# LSN_Motherboard_1_2.net
KiCad netlist of a schematic drawn in EAGLE
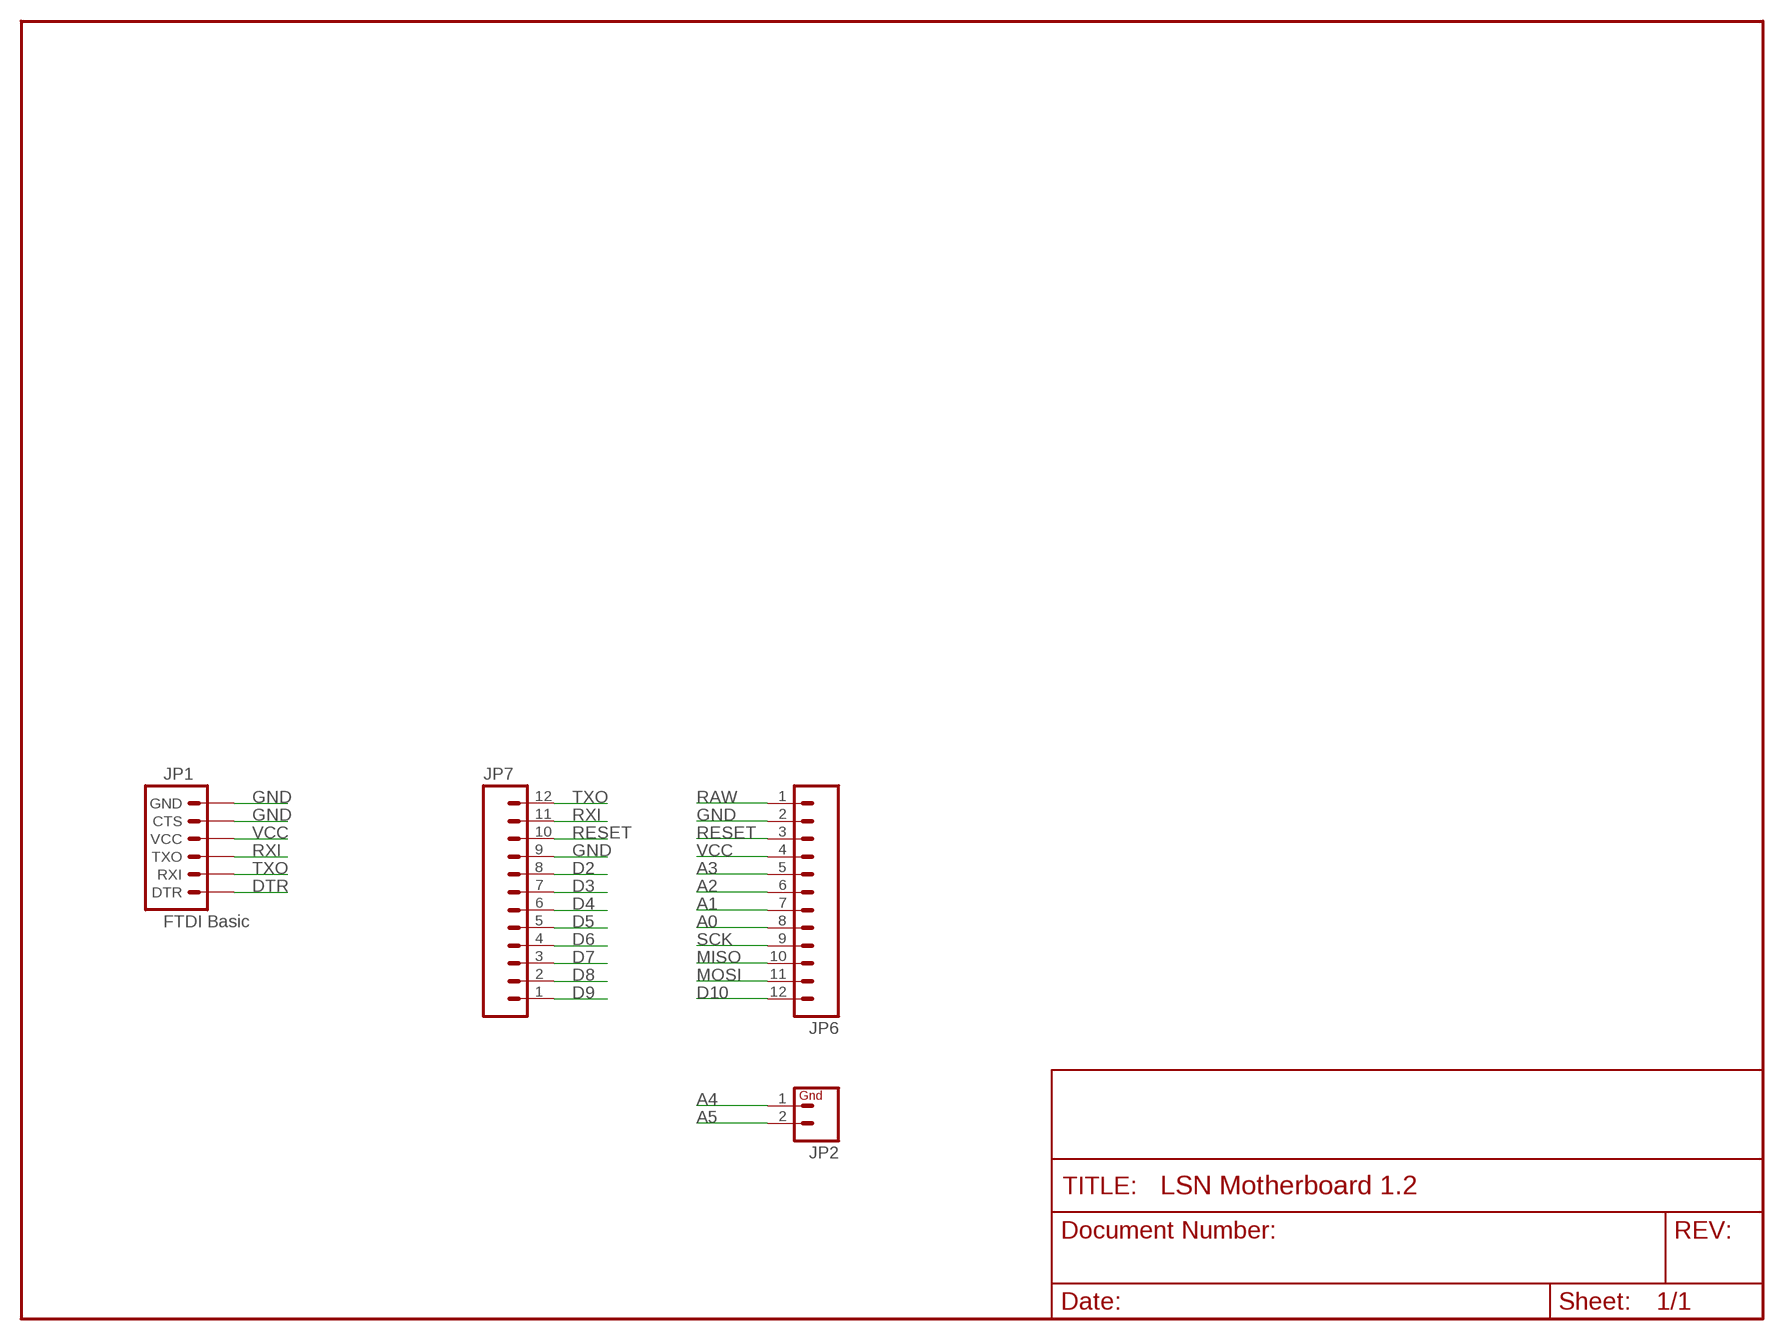
[diagram p0: schematic, sheet 1]

(export (version "E")
  (design (tool "Eeschema 10.0.6"))
  (components
    (comp (ref "JP1")
      (value "FTDI Basic")
      (footprint "eagle-import:1X06")
      (libsource (lib "eagle-import") (part "ARDUINO_SERIAL_PROGRAMPTH"))
    )
    (comp (ref "JP2")
      (value "M02PTH")
      (footprint "eagle-import:1X02")
      (libsource (lib "eagle-import") (part "M02PTH"))
    )
    (comp (ref "JP6")
      (value "M12PTH")
      (footprint "eagle-import:1X12")
      (libsource (lib "eagle-import") (part "M12PTH"))
    )
    (comp (ref "JP7")
      (value "M12PTH")
      (footprint "eagle-import:1X12")
      (libsource (lib "eagle-import") (part "M12PTH"))
    )
  )
  (nets
    (net (code "1") (name "/A0") (class "Default")
      (node (ref "JP6") (pin "8") (pinfunction "8_8") (pintype "passive"))
    )
    (net (code "2") (name "/A1") (class "Default")
      (node (ref "JP6") (pin "7") (pinfunction "7_7") (pintype "passive"))
    )
    (net (code "3") (name "/A2") (class "Default")
      (node (ref "JP6") (pin "6") (pinfunction "6_6") (pintype "passive"))
    )
    (net (code "4") (name "/A3") (class "Default")
      (node (ref "JP6") (pin "5") (pinfunction "5_5") (pintype "passive"))
    )
    (net (code "5") (name "/A4") (class "Default")
      (node (ref "JP2") (pin "1") (pinfunction "1_1") (pintype "passive"))
    )
    (net (code "6") (name "/A5") (class "Default")
      (node (ref "JP2") (pin "2") (pinfunction "2_2") (pintype "passive"))
    )
    (net (code "7") (name "/D2") (class "Default")
      (node (ref "JP7") (pin "8") (pinfunction "8_8") (pintype "passive"))
    )
    (net (code "8") (name "/D3") (class "Default")
      (node (ref "JP7") (pin "7") (pinfunction "7_7") (pintype "passive"))
    )
    (net (code "9") (name "/D4") (class "Default")
      (node (ref "JP7") (pin "6") (pinfunction "6_6") (pintype "passive"))
    )
    (net (code "10") (name "/D5") (class "Default")
      (node (ref "JP7") (pin "5") (pinfunction "5_5") (pintype "passive"))
    )
    (net (code "11") (name "/D6") (class "Default")
      (node (ref "JP7") (pin "4") (pinfunction "4_4") (pintype "passive"))
    )
    (net (code "12") (name "/D7") (class "Default")
      (node (ref "JP7") (pin "3") (pinfunction "3_3") (pintype "passive"))
    )
    (net (code "13") (name "/D8") (class "Default")
      (node (ref "JP7") (pin "2") (pinfunction "2_2") (pintype "passive"))
    )
    (net (code "14") (name "/D9") (class "Default")
      (node (ref "JP7") (pin "1") (pinfunction "1_1") (pintype "passive"))
    )
    (net (code "15") (name "/D10") (class "Default")
      (node (ref "JP6") (pin "12") (pinfunction "12_12") (pintype "passive"))
    )
    (net (code "16") (name "/DTR") (class "Default")
      (node (ref "JP1") (pin "1") (pinfunction "DTR_1") (pintype "passive"))
    )
    (net (code "17") (name "/GND") (class "Default")
      (node (ref "JP1") (pin "5") (pinfunction "CTS_5") (pintype "passive"))
      (node (ref "JP1") (pin "6") (pinfunction "GND_6") (pintype "passive"))
      (node (ref "JP6") (pin "2") (pinfunction "2_2") (pintype "passive"))
      (node (ref "JP7") (pin "9") (pinfunction "9_9") (pintype "passive"))
    )
    (net (code "18") (name "/MISO") (class "Default")
      (node (ref "JP6") (pin "10") (pinfunction "10_10") (pintype "passive"))
    )
    (net (code "19") (name "/MOSI") (class "Default")
      (node (ref "JP6") (pin "11") (pinfunction "11_11") (pintype "passive"))
    )
    (net (code "20") (name "/RAW") (class "Default")
      (node (ref "JP6") (pin "1") (pinfunction "1_1") (pintype "passive"))
    )
    (net (code "21") (name "/RESET") (class "Default")
      (node (ref "JP6") (pin "3") (pinfunction "3_3") (pintype "passive"))
      (node (ref "JP7") (pin "10") (pinfunction "10_10") (pintype "passive"))
    )
    (net (code "22") (name "/RXI") (class "Default")
      (node (ref "JP1") (pin "3") (pinfunction "TXO_3") (pintype "passive"))
      (node (ref "JP7") (pin "11") (pinfunction "11_11") (pintype "passive"))
    )
    (net (code "23") (name "/SCK") (class "Default")
      (node (ref "JP6") (pin "9") (pinfunction "9_9") (pintype "passive"))
    )
    (net (code "24") (name "/TXO") (class "Default")
      (node (ref "JP1") (pin "2") (pinfunction "RXI_2") (pintype "passive"))
      (node (ref "JP7") (pin "12") (pinfunction "12_12") (pintype "passive"))
    )
    (net (code "25") (name "/VCC") (class "Default")
      (node (ref "JP1") (pin "4") (pinfunction "VCC_4") (pintype "passive"))
      (node (ref "JP6") (pin "4") (pinfunction "4_4") (pintype "passive"))
    )
  )
)
